# HammerHeadAFE.net
KiCad netlist of a schematic drawn in Altium Designer
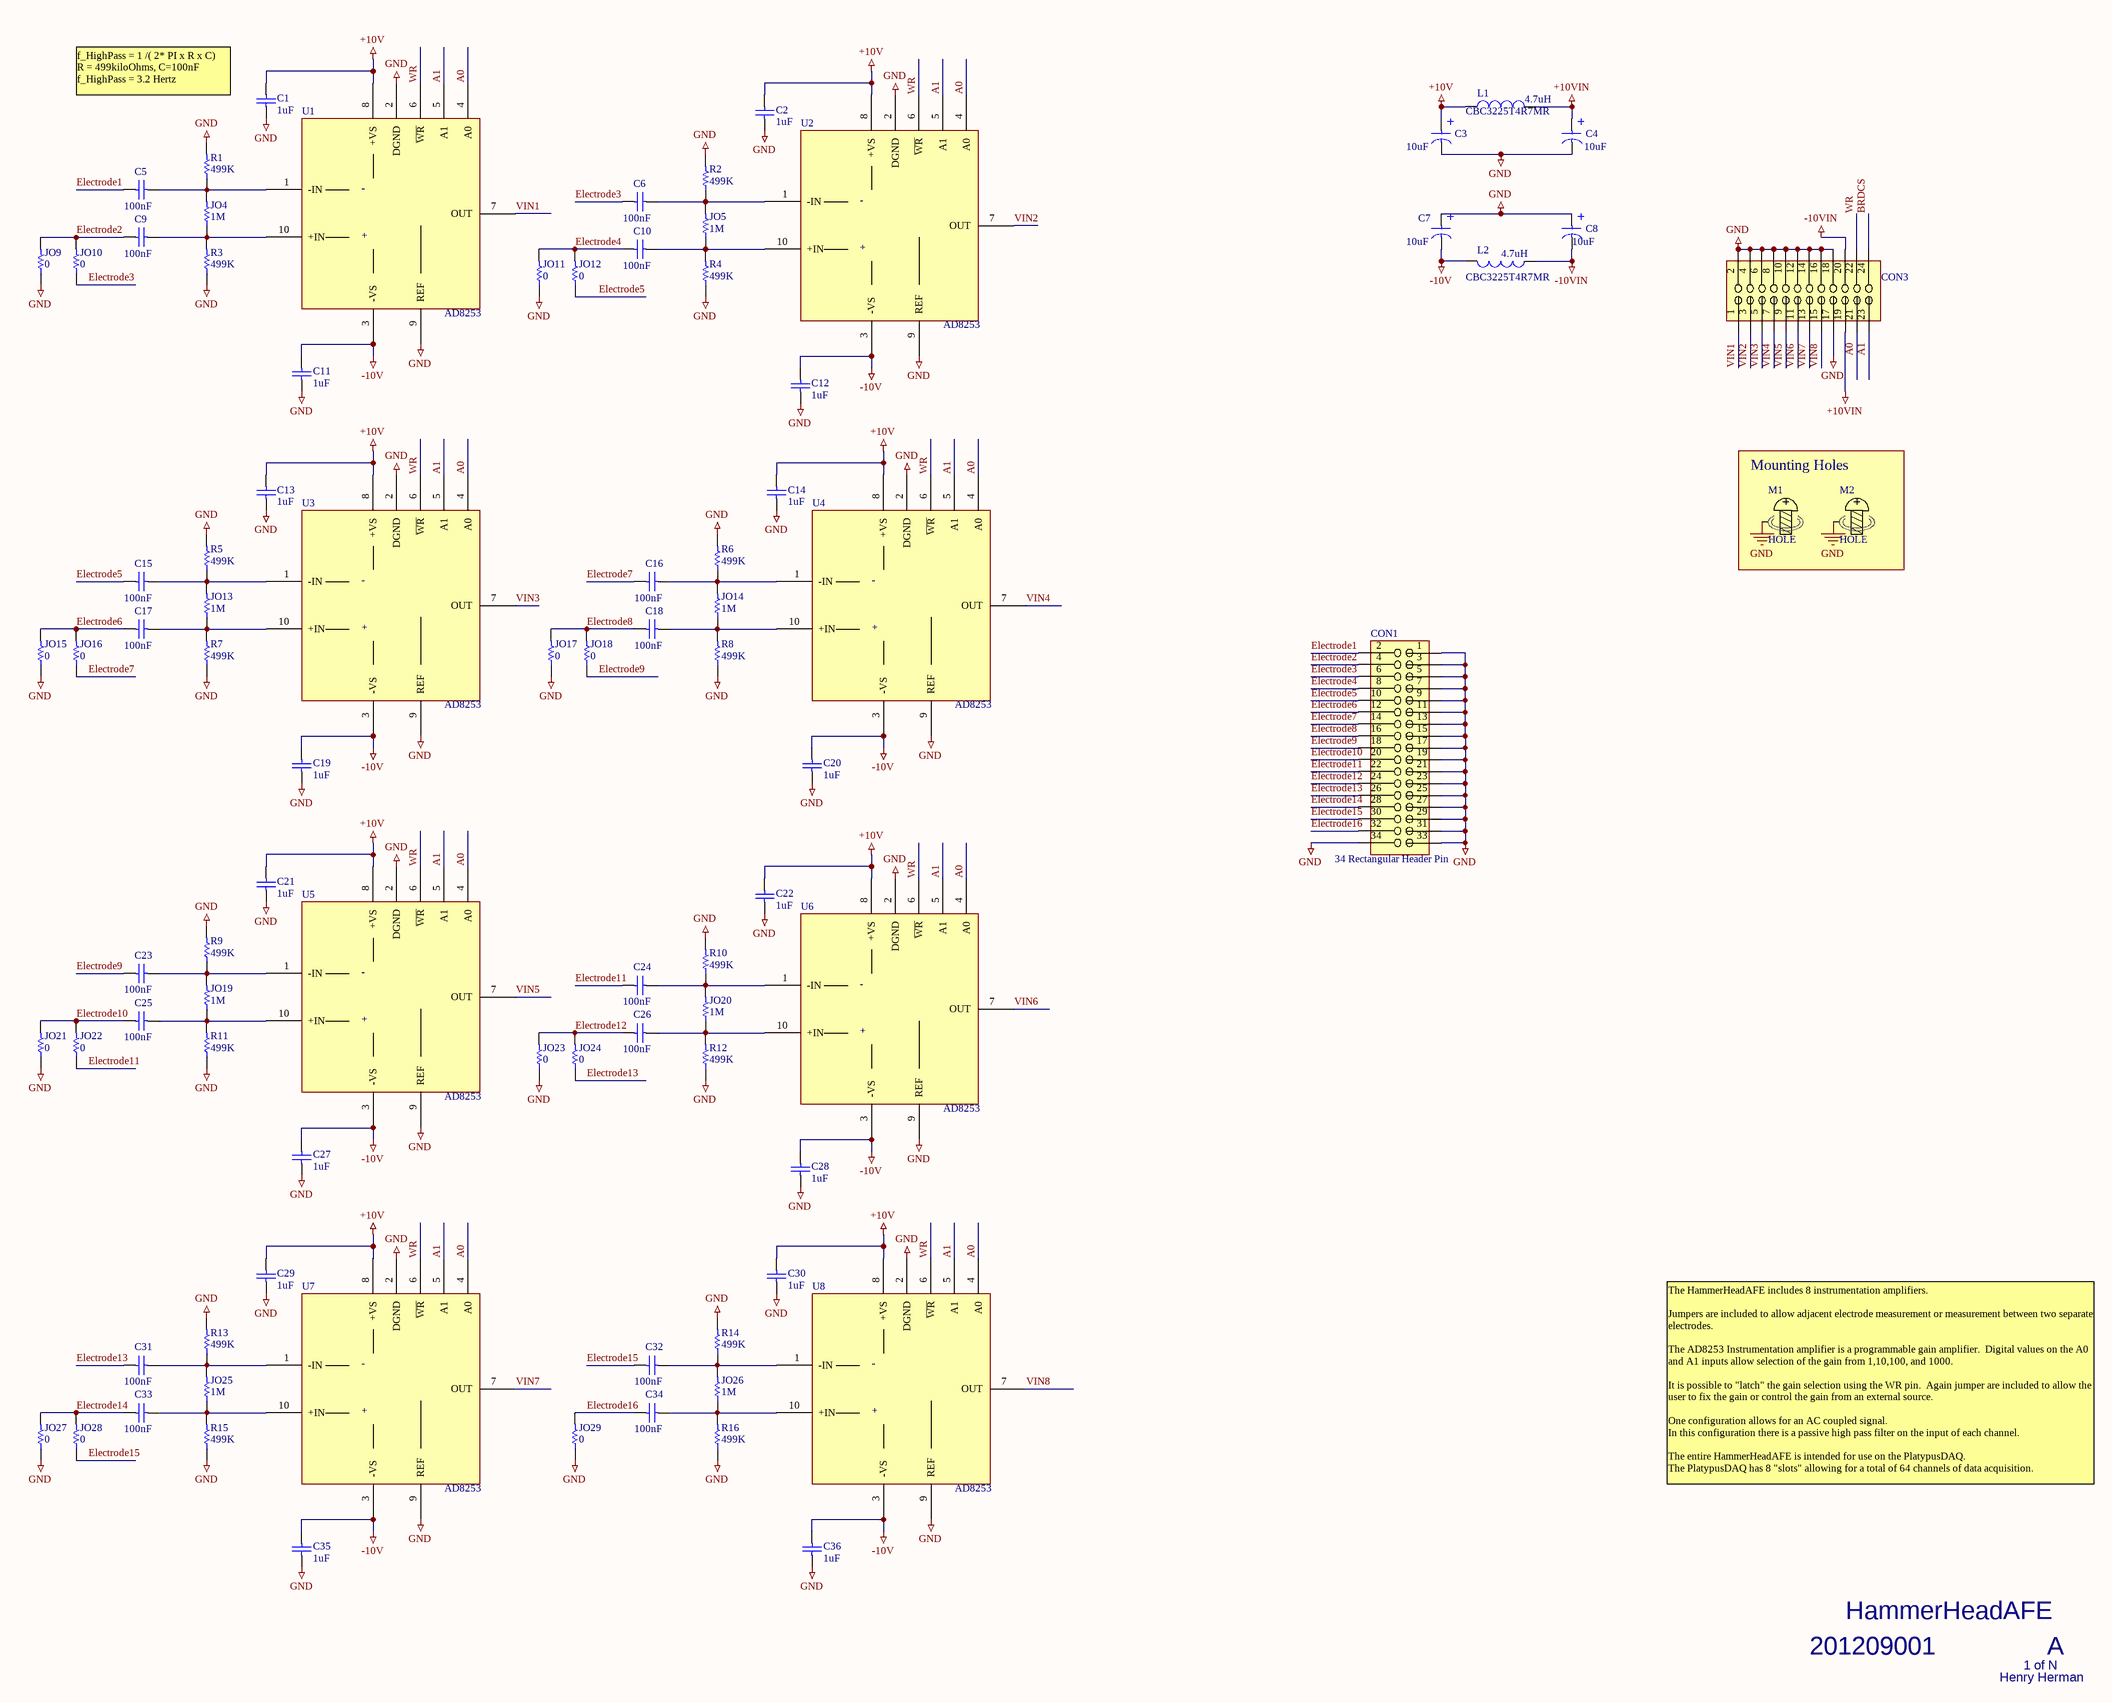
[diagram p0: HammerHeadAFE.SchDoc]

(export (version "E")
  (design (tool "Eeschema 10.0.6"))
  (components
    (comp (ref "C1")
      (value "CAP")
      (footprint "SM/C_0603")
      (description "1uF")
      (fields (field (name "LABEL") "1uF"))
      (libsource (lib "Henry1_20_2010") (part "CAP"))
    )
    (comp (ref "C2")
      (value "CAP")
      (footprint "SM/C_0603")
      (description "1uF")
      (fields (field (name "LABEL") "1uF"))
      (libsource (lib "Henry1_20_2010") (part "CAP"))
    )
    (comp (ref "C3")
      (value "CAP_POL")
      (footprint "SM/C_POL_0805")
      (description "CAP")
      (fields (field (name "LABEL") "10uF"))
      (libsource (lib "Henry1_20_2010") (part "CAP_POL"))
    )
    (comp (ref "C4")
      (value "CAP_POL")
      (footprint "SM/C_POL_0805")
      (description "CAP")
      (fields (field (name "LABEL") "10uF"))
      (libsource (lib "Henry1_20_2010") (part "CAP_POL"))
    )
    (comp (ref "C5")
      (value "CAP")
      (footprint "SM/C_0603")
      (description "100nF")
      (fields (field (name "LABEL") "100nF"))
      (libsource (lib "Henry1_20_2010") (part "CAP"))
    )
    (comp (ref "C6")
      (value "CAP")
      (footprint "SM/C_0603")
      (description "100nF")
      (fields (field (name "LABEL") "100nF"))
      (libsource (lib "Henry1_20_2010") (part "CAP"))
    )
    (comp (ref "C7")
      (value "CAP_POL")
      (footprint "SM/C_POL_0805")
      (description "CAP")
      (fields (field (name "LABEL") "10uF"))
      (libsource (lib "Henry1_20_2010") (part "CAP_POL"))
    )
    (comp (ref "C8")
      (value "CAP_POL")
      (footprint "SM/C_POL_0805")
      (description "CAP")
      (fields (field (name "LABEL") "10uF"))
      (libsource (lib "Henry1_20_2010") (part "CAP_POL"))
    )
    (comp (ref "C9")
      (value "CAP")
      (footprint "SM/C_0603")
      (description "100nF")
      (fields (field (name "LABEL") "100nF"))
      (libsource (lib "Henry1_20_2010") (part "CAP"))
    )
    (comp (ref "C10")
      (value "CAP")
      (footprint "SM/C_0603")
      (description "100nF")
      (fields (field (name "LABEL") "100nF"))
      (libsource (lib "Henry1_20_2010") (part "CAP"))
    )
    (comp (ref "C11")
      (value "CAP")
      (footprint "SM/C_0603")
      (description "1uF")
      (fields (field (name "LABEL") "1uF"))
      (libsource (lib "Henry1_20_2010") (part "CAP"))
    )
    (comp (ref "C12")
      (value "CAP")
      (footprint "SM/C_0603")
      (description "1uF")
      (fields (field (name "LABEL") "1uF"))
      (libsource (lib "Henry1_20_2010") (part "CAP"))
    )
    (comp (ref "C13")
      (value "CAP")
      (footprint "SM/C_0603")
      (description "1uF")
      (fields (field (name "LABEL") "1uF"))
      (libsource (lib "Henry1_20_2010") (part "CAP"))
    )
    (comp (ref "C14")
      (value "CAP")
      (footprint "SM/C_0603")
      (description "1uF")
      (fields (field (name "LABEL") "1uF"))
      (libsource (lib "Henry1_20_2010") (part "CAP"))
    )
    (comp (ref "C15")
      (value "CAP")
      (footprint "SM/C_0603")
      (description "100nF")
      (fields (field (name "LABEL") "100nF"))
      (libsource (lib "Henry1_20_2010") (part "CAP"))
    )
    (comp (ref "C16")
      (value "CAP")
      (footprint "SM/C_0603")
      (description "100nF")
      (fields (field (name "LABEL") "100nF"))
      (libsource (lib "Henry1_20_2010") (part "CAP"))
    )
    (comp (ref "C17")
      (value "CAP")
      (footprint "SM/C_0603")
      (description "100nF")
      (fields (field (name "LABEL") "100nF"))
      (libsource (lib "Henry1_20_2010") (part "CAP"))
    )
    (comp (ref "C18")
      (value "CAP")
      (footprint "SM/C_0603")
      (description "100nF")
      (fields (field (name "LABEL") "100nF"))
      (libsource (lib "Henry1_20_2010") (part "CAP"))
    )
    (comp (ref "C19")
      (value "CAP")
      (footprint "SM/C_0603")
      (description "1uF")
      (fields (field (name "LABEL") "1uF"))
      (libsource (lib "Henry1_20_2010") (part "CAP"))
    )
    (comp (ref "C20")
      (value "CAP")
      (footprint "SM/C_0603")
      (description "1uF")
      (fields (field (name "LABEL") "1uF"))
      (libsource (lib "Henry1_20_2010") (part "CAP"))
    )
    (comp (ref "C21")
      (value "CAP")
      (footprint "SM/C_0603")
      (description "1uF")
      (fields (field (name "LABEL") "1uF"))
      (libsource (lib "Henry1_20_2010") (part "CAP"))
    )
    (comp (ref "C22")
      (value "CAP")
      (footprint "SM/C_0603")
      (description "1uF")
      (fields (field (name "LABEL") "1uF"))
      (libsource (lib "Henry1_20_2010") (part "CAP"))
    )
    (comp (ref "C23")
      (value "CAP")
      (footprint "SM/C_0603")
      (description "100nF")
      (fields (field (name "LABEL") "100nF"))
      (libsource (lib "Henry1_20_2010") (part "CAP"))
    )
    (comp (ref "C24")
      (value "CAP")
      (footprint "SM/C_0603")
      (description "100nF")
      (fields (field (name "LABEL") "100nF"))
      (libsource (lib "Henry1_20_2010") (part "CAP"))
    )
    (comp (ref "C25")
      (value "CAP")
      (footprint "SM/C_0603")
      (description "100nF")
      (fields (field (name "LABEL") "100nF"))
      (libsource (lib "Henry1_20_2010") (part "CAP"))
    )
    (comp (ref "C26")
      (value "CAP")
      (footprint "SM/C_0603")
      (description "100nF")
      (fields (field (name "LABEL") "100nF"))
      (libsource (lib "Henry1_20_2010") (part "CAP"))
    )
    (comp (ref "C27")
      (value "CAP")
      (footprint "SM/C_0603")
      (description "1uF")
      (fields (field (name "LABEL") "1uF"))
      (libsource (lib "Henry1_20_2010") (part "CAP"))
    )
    (comp (ref "C28")
      (value "CAP")
      (footprint "SM/C_0603")
      (description "1uF")
      (fields (field (name "LABEL") "1uF"))
      (libsource (lib "Henry1_20_2010") (part "CAP"))
    )
    (comp (ref "C29")
      (value "CAP")
      (footprint "SM/C_0603")
      (description "1uF")
      (fields (field (name "LABEL") "1uF"))
      (libsource (lib "Henry1_20_2010") (part "CAP"))
    )
    (comp (ref "C30")
      (value "CAP")
      (footprint "SM/C_0603")
      (description "1uF")
      (fields (field (name "LABEL") "1uF"))
      (libsource (lib "Henry1_20_2010") (part "CAP"))
    )
    (comp (ref "C31")
      (value "CAP")
      (footprint "SM/C_0603")
      (description "100nF")
      (fields (field (name "LABEL") "100nF"))
      (libsource (lib "Henry1_20_2010") (part "CAP"))
    )
    (comp (ref "C32")
      (value "CAP")
      (footprint "SM/C_0603")
      (description "100nF")
      (fields (field (name "LABEL") "100nF"))
      (libsource (lib "Henry1_20_2010") (part "CAP"))
    )
    (comp (ref "C33")
      (value "CAP")
      (footprint "SM/C_0603")
      (description "100nF")
      (fields (field (name "LABEL") "100nF"))
      (libsource (lib "Henry1_20_2010") (part "CAP"))
    )
    (comp (ref "C34")
      (value "CAP")
      (footprint "SM/C_0603")
      (description "100nF")
      (fields (field (name "LABEL") "100nF"))
      (libsource (lib "Henry1_20_2010") (part "CAP"))
    )
    (comp (ref "C35")
      (value "CAP")
      (footprint "SM/C_0603")
      (description "1uF")
      (fields (field (name "LABEL") "1uF"))
      (libsource (lib "Henry1_20_2010") (part "CAP"))
    )
    (comp (ref "C36")
      (value "CAP")
      (footprint "SM/C_0603")
      (description "1uF")
      (fields (field (name "LABEL") "1uF"))
      (libsource (lib "Henry1_20_2010") (part "CAP"))
    )
    (comp (ref "CON1")
      (value "34 Rectangular Header Pin")
      (footprint "34Pin-Rectangular Header-SurfaceMount-100milSpacing")
      (libsource (lib "Henry1_20_2010") (part "34pinHeader"))
    )
    (comp (ref "CON3")
      (value "24pinHeader")
      (footprint "CONN-RECEPT-24PIN")
      (libsource (lib "Henry1_20_2010") (part "24pinHeader"))
    )
    (comp (ref "JO4")
      (value "1M")
      (footprint "SM/R_0603")
      (description "Resistor 1M")
      (fields (field (name "Comment") "Res") (field (name "PUBLISHER") "Altium Limited"))
      (libsource (lib "Henry1_20_2010") (part "Res"))
    )
    (comp (ref "JO5")
      (value "1M")
      (footprint "SM/R_0603")
      (description "Resistor 1M")
      (fields (field (name "Comment") "Res") (field (name "PUBLISHER") "Altium Limited"))
      (libsource (lib "Henry1_20_2010") (part "Res"))
    )
    (comp (ref "JO9")
      (value "0")
      (footprint "SM/R_0603")
      (description "Resistor")
      (fields (field (name "Comment") "Res") (field (name "PUBLISHER") "Altium Limited"))
      (libsource (lib "Henry1_20_2010") (part "Res"))
    )
    (comp (ref "JO10")
      (value "0")
      (footprint "SM/R_0603")
      (description "Resistor")
      (fields (field (name "Comment") "Res") (field (name "PUBLISHER") "Altium Limited"))
      (libsource (lib "Henry1_20_2010") (part "Res"))
    )
    (comp (ref "JO11")
      (value "0")
      (footprint "SM/R_0603")
      (description "Resistor")
      (fields (field (name "Comment") "Res") (field (name "PUBLISHER") "Altium Limited"))
      (libsource (lib "Henry1_20_2010") (part "Res"))
    )
    (comp (ref "JO12")
      (value "0")
      (footprint "SM/R_0603")
      (description "Resistor")
      (fields (field (name "Comment") "Res") (field (name "PUBLISHER") "Altium Limited"))
      (libsource (lib "Henry1_20_2010") (part "Res"))
    )
    (comp (ref "JO13")
      (value "1M")
      (footprint "SM/R_0603")
      (description "Resistor 1M")
      (fields (field (name "Comment") "Res") (field (name "PUBLISHER") "Altium Limited"))
      (libsource (lib "Henry1_20_2010") (part "Res"))
    )
    (comp (ref "JO14")
      (value "1M")
      (footprint "SM/R_0603")
      (description "Resistor 1M")
      (fields (field (name "Comment") "Res") (field (name "PUBLISHER") "Altium Limited"))
      (libsource (lib "Henry1_20_2010") (part "Res"))
    )
    (comp (ref "JO15")
      (value "0")
      (footprint "SM/R_0603")
      (description "Resistor")
      (fields (field (name "Comment") "Res") (field (name "PUBLISHER") "Altium Limited"))
      (libsource (lib "Henry1_20_2010") (part "Res"))
    )
    (comp (ref "JO16")
      (value "0")
      (footprint "SM/R_0603")
      (description "Resistor")
      (fields (field (name "Comment") "Res") (field (name "PUBLISHER") "Altium Limited"))
      (libsource (lib "Henry1_20_2010") (part "Res"))
    )
    (comp (ref "JO17")
      (value "0")
      (footprint "SM/R_0603")
      (description "Resistor")
      (fields (field (name "Comment") "Res") (field (name "PUBLISHER") "Altium Limited"))
      (libsource (lib "Henry1_20_2010") (part "Res"))
    )
    (comp (ref "JO18")
      (value "0")
      (footprint "SM/R_0603")
      (description "Resistor")
      (fields (field (name "Comment") "Res") (field (name "PUBLISHER") "Altium Limited"))
      (libsource (lib "Henry1_20_2010") (part "Res"))
    )
    (comp (ref "JO19")
      (value "1M")
      (footprint "SM/R_0603")
      (description "Resistor 1M")
      (fields (field (name "Comment") "Res") (field (name "PUBLISHER") "Altium Limited"))
      (libsource (lib "Henry1_20_2010") (part "Res"))
    )
    (comp (ref "JO20")
      (value "1M")
      (footprint "SM/R_0603")
      (description "Resistor 1M")
      (fields (field (name "Comment") "Res") (field (name "PUBLISHER") "Altium Limited"))
      (libsource (lib "Henry1_20_2010") (part "Res"))
    )
    (comp (ref "JO21")
      (value "0")
      (footprint "SM/R_0603")
      (description "Resistor")
      (fields (field (name "Comment") "Res") (field (name "PUBLISHER") "Altium Limited"))
      (libsource (lib "Henry1_20_2010") (part "Res"))
    )
    (comp (ref "JO22")
      (value "0")
      (footprint "SM/R_0603")
      (description "Resistor")
      (fields (field (name "Comment") "Res") (field (name "PUBLISHER") "Altium Limited"))
      (libsource (lib "Henry1_20_2010") (part "Res"))
    )
    (comp (ref "JO23")
      (value "0")
      (footprint "SM/R_0603")
      (description "Resistor")
      (fields (field (name "Comment") "Res") (field (name "PUBLISHER") "Altium Limited"))
      (libsource (lib "Henry1_20_2010") (part "Res"))
    )
    (comp (ref "JO24")
      (value "0")
      (footprint "SM/R_0603")
      (description "Resistor")
      (fields (field (name "Comment") "Res") (field (name "PUBLISHER") "Altium Limited"))
      (libsource (lib "Henry1_20_2010") (part "Res"))
    )
    (comp (ref "JO25")
      (value "1M")
      (footprint "SM/R_0603")
      (description "Resistor 1M")
      (fields (field (name "Comment") "Res") (field (name "PUBLISHER") "Altium Limited"))
      (libsource (lib "Henry1_20_2010") (part "Res"))
    )
    (comp (ref "JO26")
      (value "1M")
      (footprint "SM/R_0603")
      (description "Resistor 1M")
      (fields (field (name "Comment") "Res") (field (name "PUBLISHER") "Altium Limited"))
      (libsource (lib "Henry1_20_2010") (part "Res"))
    )
    (comp (ref "JO27")
      (value "0")
      (footprint "SM/R_0603")
      (description "Resistor")
      (fields (field (name "Comment") "Res") (field (name "PUBLISHER") "Altium Limited"))
      (libsource (lib "Henry1_20_2010") (part "Res"))
    )
    (comp (ref "JO28")
      (value "0")
      (footprint "SM/R_0603")
      (description "Resistor")
      (fields (field (name "Comment") "Res") (field (name "PUBLISHER") "Altium Limited"))
      (libsource (lib "Henry1_20_2010") (part "Res"))
    )
    (comp (ref "JO29")
      (value "0")
      (footprint "SM/R_0603")
      (description "Resistor")
      (fields (field (name "Comment") "Res") (field (name "PUBLISHER") "Altium Limited"))
      (libsource (lib "Henry1_20_2010") (part "Res"))
    )
    (comp (ref "L1")
      (value "CBC3225T4R7MR")
      (footprint "SM/L_0805")
      (fields (field (name "ALTIUM_VALUE") "4.7uH"))
      (libsource (lib "Henry1_20_2010") (part "Inductor"))
    )
    (comp (ref "L2")
      (value "CBC3225T4R7MR")
      (footprint "SM/L_0805")
      (fields (field (name "ALTIUM_VALUE") "4.7uH"))
      (libsource (lib "Henry1_20_2010") (part "Inductor"))
    )
    (comp (ref "M1")
      (value "HOLE")
      (footprint "MOUNTING_HOLE-125mil")
      (libsource (lib "Henry1_20_2010") (part "MountingHole"))
    )
    (comp (ref "M2")
      (value "HOLE")
      (footprint "MOUNTING_HOLE-125mil")
      (libsource (lib "Henry1_20_2010") (part "MountingHole"))
    )
    (comp (ref "R1")
      (value "499K")
      (footprint "SM/R_0603")
      (description "Resistor")
      (fields (field (name "Comment") "Res") (field (name "PUBLISHER") "Altium Limited"))
      (libsource (lib "Henry1_20_2010") (part "Res"))
    )
    (comp (ref "R2")
      (value "499K")
      (footprint "SM/R_0603")
      (description "Resistor")
      (fields (field (name "Comment") "Res") (field (name "PUBLISHER") "Altium Limited"))
      (libsource (lib "Henry1_20_2010") (part "Res"))
    )
    (comp (ref "R3")
      (value "499K")
      (footprint "SM/R_0603")
      (description "Resistor")
      (fields (field (name "Comment") "Res") (field (name "PUBLISHER") "Altium Limited"))
      (libsource (lib "Henry1_20_2010") (part "Res"))
    )
    (comp (ref "R4")
      (value "499K")
      (footprint "SM/R_0603")
      (description "Resistor")
      (fields (field (name "Comment") "Res") (field (name "PUBLISHER") "Altium Limited"))
      (libsource (lib "Henry1_20_2010") (part "Res"))
    )
    (comp (ref "R5")
      (value "499K")
      (footprint "SM/R_0603")
      (description "Resistor")
      (fields (field (name "Comment") "Res") (field (name "PUBLISHER") "Altium Limited"))
      (libsource (lib "Henry1_20_2010") (part "Res"))
    )
    (comp (ref "R6")
      (value "499K")
      (footprint "SM/R_0603")
      (description "Resistor")
      (fields (field (name "Comment") "Res") (field (name "PUBLISHER") "Altium Limited"))
      (libsource (lib "Henry1_20_2010") (part "Res"))
    )
    (comp (ref "R7")
      (value "499K")
      (footprint "SM/R_0603")
      (description "Resistor")
      (fields (field (name "Comment") "Res") (field (name "PUBLISHER") "Altium Limited"))
      (libsource (lib "Henry1_20_2010") (part "Res"))
    )
    (comp (ref "R8")
      (value "499K")
      (footprint "SM/R_0603")
      (description "Resistor")
      (fields (field (name "Comment") "Res") (field (name "PUBLISHER") "Altium Limited"))
      (libsource (lib "Henry1_20_2010") (part "Res"))
    )
    (comp (ref "R9")
      (value "499K")
      (footprint "SM/R_0603")
      (description "Resistor")
      (fields (field (name "Comment") "Res") (field (name "PUBLISHER") "Altium Limited"))
      (libsource (lib "Henry1_20_2010") (part "Res"))
    )
    (comp (ref "R10")
      (value "499K")
      (footprint "SM/R_0603")
      (description "Resistor")
      (fields (field (name "Comment") "Res") (field (name "PUBLISHER") "Altium Limited"))
      (libsource (lib "Henry1_20_2010") (part "Res"))
    )
    (comp (ref "R11")
      (value "499K")
      (footprint "SM/R_0603")
      (description "Resistor")
      (fields (field (name "Comment") "Res") (field (name "PUBLISHER") "Altium Limited"))
      (libsource (lib "Henry1_20_2010") (part "Res"))
    )
    (comp (ref "R12")
      (value "499K")
      (footprint "SM/R_0603")
      (description "Resistor")
      (fields (field (name "Comment") "Res") (field (name "PUBLISHER") "Altium Limited"))
      (libsource (lib "Henry1_20_2010") (part "Res"))
    )
    (comp (ref "R13")
      (value "499K")
      (footprint "SM/R_0603")
      (description "Resistor")
      (fields (field (name "Comment") "Res") (field (name "PUBLISHER") "Altium Limited"))
      (libsource (lib "Henry1_20_2010") (part "Res"))
    )
    (comp (ref "R14")
      (value "499K")
      (footprint "SM/R_0603")
      (description "Resistor")
      (fields (field (name "Comment") "Res") (field (name "PUBLISHER") "Altium Limited"))
      (libsource (lib "Henry1_20_2010") (part "Res"))
    )
    (comp (ref "R15")
      (value "499K")
      (footprint "SM/R_0603")
      (description "Resistor")
      (fields (field (name "Comment") "Res") (field (name "PUBLISHER") "Altium Limited"))
      (libsource (lib "Henry1_20_2010") (part "Res"))
    )
    (comp (ref "R16")
      (value "499K")
      (footprint "SM/R_0603")
      (description "Resistor")
      (fields (field (name "Comment") "Res") (field (name "PUBLISHER") "Altium Limited"))
      (libsource (lib "Henry1_20_2010") (part "Res"))
    )
    (comp (ref "U1")
      (value "AD8253")
      (footprint "MSOP-10-lead/AnalogDevices")
      (libsource (lib "Henry1_20_2010") (part "AD8253"))
    )
    (comp (ref "U2")
      (value "AD8253")
      (footprint "MSOP-10-lead/AnalogDevices")
      (libsource (lib "Henry1_20_2010") (part "AD8253"))
    )
    (comp (ref "U3")
      (value "AD8253")
      (footprint "MSOP-10-lead/AnalogDevices")
      (libsource (lib "Henry1_20_2010") (part "AD8253"))
    )
    (comp (ref "U4")
      (value "AD8253")
      (footprint "MSOP-10-lead/AnalogDevices")
      (libsource (lib "Henry1_20_2010") (part "AD8253"))
    )
    (comp (ref "U5")
      (value "AD8253")
      (footprint "MSOP-10-lead/AnalogDevices")
      (libsource (lib "Henry1_20_2010") (part "AD8253"))
    )
    (comp (ref "U6")
      (value "AD8253")
      (footprint "MSOP-10-lead/AnalogDevices")
      (libsource (lib "Henry1_20_2010") (part "AD8253"))
    )
    (comp (ref "U7")
      (value "AD8253")
      (footprint "MSOP-10-lead/AnalogDevices")
      (libsource (lib "Henry1_20_2010") (part "AD8253"))
    )
    (comp (ref "U8")
      (value "AD8253")
      (footprint "MSOP-10-lead/AnalogDevices")
      (libsource (lib "Henry1_20_2010") (part "AD8253"))
    )
  )
  (nets
    (net (code "1") (name "+10V") (class "Default")
      (node (ref "C1") (pin "1") (pinfunction "1_1") (pintype "passive"))
      (node (ref "C13") (pin "1") (pinfunction "1_1") (pintype "passive"))
      (node (ref "C14") (pin "1") (pinfunction "1_1") (pintype "passive"))
      (node (ref "C2") (pin "1") (pinfunction "1_1") (pintype "passive"))
      (node (ref "C21") (pin "1") (pinfunction "1_1") (pintype "passive"))
      (node (ref "C22") (pin "1") (pinfunction "1_1") (pintype "passive"))
      (node (ref "C29") (pin "1") (pinfunction "1_1") (pintype "passive"))
      (node (ref "C3") (pin "1") (pinfunction "1_1") (pintype "passive"))
      (node (ref "C30") (pin "1") (pinfunction "1_1") (pintype "passive"))
      (node (ref "L1") (pin "1") (pinfunction "1_1") (pintype "passive"))
      (node (ref "U1") (pin "8") (pinfunction "+VS_8") (pintype "passive"))
      (node (ref "U2") (pin "8") (pinfunction "+VS_8") (pintype "passive"))
      (node (ref "U3") (pin "8") (pinfunction "+VS_8") (pintype "passive"))
      (node (ref "U4") (pin "8") (pinfunction "+VS_8") (pintype "passive"))
      (node (ref "U5") (pin "8") (pinfunction "+VS_8") (pintype "passive"))
      (node (ref "U6") (pin "8") (pinfunction "+VS_8") (pintype "passive"))
      (node (ref "U7") (pin "8") (pinfunction "+VS_8") (pintype "passive"))
      (node (ref "U8") (pin "8") (pinfunction "+VS_8") (pintype "passive"))
    )
    (net (code "2") (name "+10VIN") (class "Default")
      (node (ref "C4") (pin "1") (pinfunction "1_1") (pintype "passive"))
      (node (ref "CON3") (pin "19") (pinfunction "19_19") (pintype "passive"))
      (node (ref "L1") (pin "2") (pinfunction "2_2") (pintype "passive"))
    )
    (net (code "3") (name "-10V") (class "Default")
      (node (ref "C11") (pin "1") (pinfunction "1_1") (pintype "passive"))
      (node (ref "C12") (pin "1") (pinfunction "1_1") (pintype "passive"))
      (node (ref "C19") (pin "1") (pinfunction "1_1") (pintype "passive"))
      (node (ref "C20") (pin "1") (pinfunction "1_1") (pintype "passive"))
      (node (ref "C27") (pin "1") (pinfunction "1_1") (pintype "passive"))
      (node (ref "C28") (pin "1") (pinfunction "1_1") (pintype "passive"))
      (node (ref "C35") (pin "1") (pinfunction "1_1") (pintype "passive"))
      (node (ref "C36") (pin "1") (pinfunction "1_1") (pintype "passive"))
      (node (ref "C7") (pin "2") (pinfunction "2_2") (pintype "passive"))
      (node (ref "L2") (pin "2") (pinfunction "2_2") (pintype "passive"))
      (node (ref "U1") (pin "3") (pinfunction "-VS_3") (pintype "passive"))
      (node (ref "U2") (pin "3") (pinfunction "-VS_3") (pintype "passive"))
      (node (ref "U3") (pin "3") (pinfunction "-VS_3") (pintype "passive"))
      (node (ref "U4") (pin "3") (pinfunction "-VS_3") (pintype "passive"))
      (node (ref "U5") (pin "3") (pinfunction "-VS_3") (pintype "passive"))
      (node (ref "U6") (pin "3") (pinfunction "-VS_3") (pintype "passive"))
      (node (ref "U7") (pin "3") (pinfunction "-VS_3") (pintype "passive"))
      (node (ref "U8") (pin "3") (pinfunction "-VS_3") (pintype "passive"))
    )
    (net (code "4") (name "-10VIN") (class "Default")
      (node (ref "C8") (pin "2") (pinfunction "2_2") (pintype "passive"))
      (node (ref "CON3") (pin "20") (pinfunction "20_20") (pintype "passive"))
      (node (ref "L2") (pin "1") (pinfunction "1_1") (pintype "passive"))
    )
    (net (code "5") (name "/A0") (class "Default")
      (node (ref "CON3") (pin "21") (pinfunction "21_21") (pintype "passive"))
      (node (ref "U1") (pin "4") (pinfunction "A0_4") (pintype "passive"))
      (node (ref "U2") (pin "4") (pinfunction "A0_4") (pintype "passive"))
      (node (ref "U3") (pin "4") (pinfunction "A0_4") (pintype "passive"))
      (node (ref "U4") (pin "4") (pinfunction "A0_4") (pintype "passive"))
      (node (ref "U5") (pin "4") (pinfunction "A0_4") (pintype "passive"))
      (node (ref "U6") (pin "4") (pinfunction "A0_4") (pintype "passive"))
      (node (ref "U7") (pin "4") (pinfunction "A0_4") (pintype "passive"))
      (node (ref "U8") (pin "4") (pinfunction "A0_4") (pintype "passive"))
    )
    (net (code "6") (name "/A1") (class "Default")
      (node (ref "CON3") (pin "23") (pinfunction "23_23") (pintype "passive"))
      (node (ref "U1") (pin "5") (pinfunction "A1_5") (pintype "passive"))
      (node (ref "U2") (pin "5") (pinfunction "A1_5") (pintype "passive"))
      (node (ref "U3") (pin "5") (pinfunction "A1_5") (pintype "passive"))
      (node (ref "U4") (pin "5") (pinfunction "A1_5") (pintype "passive"))
      (node (ref "U5") (pin "5") (pinfunction "A1_5") (pintype "passive"))
      (node (ref "U6") (pin "5") (pinfunction "A1_5") (pintype "passive"))
      (node (ref "U7") (pin "5") (pinfunction "A1_5") (pintype "passive"))
      (node (ref "U8") (pin "5") (pinfunction "A1_5") (pintype "passive"))
    )
    (net (code "7") (name "/BRDCS") (class "Default")
      (node (ref "CON3") (pin "24") (pinfunction "24_24") (pintype "passive"))
    )
    (net (code "8") (name "/Electrode1") (class "Default")
      (node (ref "C5") (pin "1") (pinfunction "1_1") (pintype "passive"))
      (node (ref "CON1") (pin "2") (pinfunction "2_2") (pintype "passive"))
    )
    (net (code "9") (name "/Electrode2") (class "Default")
      (node (ref "C9") (pin "1") (pinfunction "1_1") (pintype "passive"))
      (node (ref "CON1") (pin "4") (pinfunction "4_4") (pintype "passive"))
      (node (ref "JO10") (pin "2") (pinfunction "2_2") (pintype "passive"))
      (node (ref "JO9") (pin "2") (pinfunction "2_2") (pintype "passive"))
    )
    (net (code "10") (name "/Electrode3") (class "Default")
      (node (ref "C6") (pin "1") (pinfunction "1_1") (pintype "passive"))
      (node (ref "CON1") (pin "6") (pinfunction "6_6") (pintype "passive"))
      (node (ref "JO10") (pin "1") (pinfunction "1_1") (pintype "passive"))
    )
    (net (code "11") (name "/Electrode4") (class "Default")
      (node (ref "C10") (pin "1") (pinfunction "1_1") (pintype "passive"))
      (node (ref "CON1") (pin "8") (pinfunction "8_8") (pintype "passive"))
      (node (ref "JO11") (pin "2") (pinfunction "2_2") (pintype "passive"))
      (node (ref "JO12") (pin "2") (pinfunction "2_2") (pintype "passive"))
    )
    (net (code "12") (name "/Electrode5") (class "Default")
      (node (ref "C15") (pin "1") (pinfunction "1_1") (pintype "passive"))
      (node (ref "CON1") (pin "10") (pinfunction "10_10") (pintype "passive"))
      (node (ref "JO12") (pin "1") (pinfunction "1_1") (pintype "passive"))
    )
    (net (code "13") (name "/Electrode6") (class "Default")
      (node (ref "C17") (pin "1") (pinfunction "1_1") (pintype "passive"))
      (node (ref "CON1") (pin "12") (pinfunction "12_12") (pintype "passive"))
      (node (ref "JO15") (pin "2") (pinfunction "2_2") (pintype "passive"))
      (node (ref "JO16") (pin "2") (pinfunction "2_2") (pintype "passive"))
    )
    (net (code "14") (name "/Electrode7") (class "Default")
      (node (ref "C16") (pin "1") (pinfunction "1_1") (pintype "passive"))
      (node (ref "CON1") (pin "14") (pinfunction "14_14") (pintype "passive"))
      (node (ref "JO16") (pin "1") (pinfunction "1_1") (pintype "passive"))
    )
    (net (code "15") (name "/Electrode8") (class "Default")
      (node (ref "C18") (pin "1") (pinfunction "1_1") (pintype "passive"))
      (node (ref "CON1") (pin "16") (pinfunction "16_16") (pintype "passive"))
      (node (ref "JO17") (pin "2") (pinfunction "2_2") (pintype "passive"))
      (node (ref "JO18") (pin "2") (pinfunction "2_2") (pintype "passive"))
    )
    (net (code "16") (name "/Electrode9") (class "Default")
      (node (ref "C23") (pin "1") (pinfunction "1_1") (pintype "passive"))
      (node (ref "CON1") (pin "18") (pinfunction "18_18") (pintype "passive"))
      (node (ref "JO18") (pin "1") (pinfunction "1_1") (pintype "passive"))
    )
    (net (code "17") (name "/Electrode10") (class "Default")
      (node (ref "C25") (pin "1") (pinfunction "1_1") (pintype "passive"))
      (node (ref "CON1") (pin "20") (pinfunction "20_20") (pintype "passive"))
      (node (ref "JO21") (pin "2") (pinfunction "2_2") (pintype "passive"))
      (node (ref "JO22") (pin "2") (pinfunction "2_2") (pintype "passive"))
    )
    (net (code "18") (name "/Electrode11") (class "Default")
      (node (ref "C24") (pin "1") (pinfunction "1_1") (pintype "passive"))
      (node (ref "CON1") (pin "22") (pinfunction "22_22") (pintype "passive"))
      (node (ref "JO22") (pin "1") (pinfunction "1_1") (pintype "passive"))
    )
    (net (code "19") (name "/Electrode12") (class "Default")
      (node (ref "C26") (pin "1") (pinfunction "1_1") (pintype "passive"))
      (node (ref "CON1") (pin "24") (pinfunction "24_24") (pintype "passive"))
      (node (ref "JO23") (pin "2") (pinfunction "2_2") (pintype "passive"))
      (node (ref "JO24") (pin "2") (pinfunction "2_2") (pintype "passive"))
    )
    (net (code "20") (name "/Electrode13") (class "Default")
      (node (ref "C31") (pin "1") (pinfunction "1_1") (pintype "passive"))
      (node (ref "CON1") (pin "26") (pinfunction "26_26") (pintype "passive"))
      (node (ref "JO24") (pin "1") (pinfunction "1_1") (pintype "passive"))
    )
    (net (code "21") (name "/Electrode14") (class "Default")
      (node (ref "C33") (pin "1") (pinfunction "1_1") (pintype "passive"))
      (node (ref "CON1") (pin "28") (pinfunction "28_28") (pintype "passive"))
      (node (ref "JO27") (pin "2") (pinfunction "2_2") (pintype "passive"))
      (node (ref "JO28") (pin "2") (pinfunction "2_2") (pintype "passive"))
    )
    (net (code "22") (name "/Electrode15") (class "Default")
      (node (ref "C32") (pin "1") (pinfunction "1_1") (pintype "passive"))
      (node (ref "CON1") (pin "30") (pinfunction "30_30") (pintype "passive"))
      (node (ref "JO28") (pin "1") (pinfunction "1_1") (pintype "passive"))
    )
    (net (code "23") (name "/Electrode16") (class "Default")
      (node (ref "C34") (pin "1") (pinfunction "1_1") (pintype "passive"))
      (node (ref "CON1") (pin "32") (pinfunction "32_32") (pintype "passive"))
      (node (ref "JO29") (pin "2") (pinfunction "2_2") (pintype "passive"))
    )
    (net (code "24") (name "/VIN1") (class "Default")
      (node (ref "CON3") (pin "1") (pinfunction "1_1") (pintype "passive"))
      (node (ref "U1") (pin "7") (pinfunction "OUT_7") (pintype "passive"))
    )
    (net (code "25") (name "/VIN2") (class "Default")
      (node (ref "CON3") (pin "3") (pinfunction "3_3") (pintype "passive"))
      (node (ref "U2") (pin "7") (pinfunction "OUT_7") (pintype "passive"))
    )
    (net (code "26") (name "/VIN3") (class "Default")
      (node (ref "CON3") (pin "5") (pinfunction "5_5") (pintype "passive"))
      (node (ref "U3") (pin "7") (pinfunction "OUT_7") (pintype "passive"))
    )
    (net (code "27") (name "/VIN4") (class "Default")
      (node (ref "CON3") (pin "7") (pinfunction "7_7") (pintype "passive"))
      (node (ref "U4") (pin "7") (pinfunction "OUT_7") (pintype "passive"))
    )
    (net (code "28") (name "/VIN5") (class "Default")
      (node (ref "CON3") (pin "9") (pinfunction "9_9") (pintype "passive"))
      (node (ref "U5") (pin "7") (pinfunction "OUT_7") (pintype "passive"))
    )
    (net (code "29") (name "/VIN6") (class "Default")
      (node (ref "CON3") (pin "11") (pinfunction "11_11") (pintype "passive"))
      (node (ref "U6") (pin "7") (pinfunction "OUT_7") (pintype "passive"))
    )
    (net (code "30") (name "/VIN7") (class "Default")
      (node (ref "CON3") (pin "13") (pinfunction "13_13") (pintype "passive"))
      (node (ref "U7") (pin "7") (pinfunction "OUT_7") (pintype "passive"))
    )
    (net (code "31") (name "/VIN8") (class "Default")
      (node (ref "CON3") (pin "15") (pinfunction "15_15") (pintype "passive"))
      (node (ref "U8") (pin "7") (pinfunction "OUT_7") (pintype "passive"))
    )
    (net (code "32") (name "/WR") (class "Default")
      (node (ref "CON3") (pin "22") (pinfunction "22_22") (pintype "passive"))
      (node (ref "U1") (pin "6") (pinfunction "~{WR}_6") (pintype "passive"))
      (node (ref "U2") (pin "6") (pinfunction "~{WR}_6") (pintype "passive"))
      (node (ref "U3") (pin "6") (pinfunction "~{WR}_6") (pintype "passive"))
      (node (ref "U4") (pin "6") (pinfunction "~{WR}_6") (pintype "passive"))
      (node (ref "U5") (pin "6") (pinfunction "~{WR}_6") (pintype "passive"))
      (node (ref "U6") (pin "6") (pinfunction "~{WR}_6") (pintype "passive"))
      (node (ref "U7") (pin "6") (pinfunction "~{WR}_6") (pintype "passive"))
      (node (ref "U8") (pin "6") (pinfunction "~{WR}_6") (pintype "passive"))
    )
    (net (code "33") (name "GND") (class "Default")
      (node (ref "C1") (pin "2") (pinfunction "2_2") (pintype "passive"))
      (node (ref "C11") (pin "2") (pinfunction "2_2") (pintype "passive"))
      (node (ref "C12") (pin "2") (pinfunction "2_2") (pintype "passive"))
      (node (ref "C13") (pin "2") (pinfunction "2_2") (pintype "passive"))
      (node (ref "C14") (pin "2") (pinfunction "2_2") (pintype "passive"))
      (node (ref "C19") (pin "2") (pinfunction "2_2") (pintype "passive"))
      (node (ref "C2") (pin "2") (pinfunction "2_2") (pintype "passive"))
      (node (ref "C20") (pin "2") (pinfunction "2_2") (pintype "passive"))
      (node (ref "C21") (pin "2") (pinfunction "2_2") (pintype "passive"))
      (node (ref "C22") (pin "2") (pinfunction "2_2") (pintype "passive"))
      (node (ref "C27") (pin "2") (pinfunction "2_2") (pintype "passive"))
      (node (ref "C28") (pin "2") (pinfunction "2_2") (pintype "passive"))
      (node (ref "C29") (pin "2") (pinfunction "2_2") (pintype "passive"))
      (node (ref "C3") (pin "2") (pinfunction "2_2") (pintype "passive"))
      (node (ref "C30") (pin "2") (pinfunction "2_2") (pintype "passive"))
      (node (ref "C35") (pin "2") (pinfunction "2_2") (pintype "passive"))
      (node (ref "C36") (pin "2") (pinfunction "2_2") (pintype "passive"))
      (node (ref "C4") (pin "2") (pinfunction "2_2") (pintype "passive"))
      (node (ref "C7") (pin "1") (pinfunction "1_1") (pintype "passive"))
      (node (ref "C8") (pin "1") (pinfunction "1_1") (pintype "passive"))
      (node (ref "CON1") (pin "1") (pinfunction "1_1") (pintype "passive"))
      (node (ref "CON1") (pin "11") (pinfunction "11_11") (pintype "passive"))
      (node (ref "CON1") (pin "13") (pinfunction "13_13") (pintype "passive"))
      (node (ref "CON1") (pin "15") (pinfunction "15_15") (pintype "passive"))
      (node (ref "CON1") (pin "17") (pinfunction "17_17") (pintype "passive"))
      (node (ref "CON1") (pin "19") (pinfunction "19_19") (pintype "passive"))
      (node (ref "CON1") (pin "21") (pinfunction "21_21") (pintype "passive"))
      (node (ref "CON1") (pin "23") (pinfunction "23_23") (pintype "passive"))
      (node (ref "CON1") (pin "25") (pinfunction "25_25") (pintype "passive"))
      (node (ref "CON1") (pin "27") (pinfunction "27_27") (pintype "passive"))
      (node (ref "CON1") (pin "29") (pinfunction "29_29") (pintype "passive"))
      (node (ref "CON1") (pin "3") (pinfunction "3_3") (pintype "passive"))
      (node (ref "CON1") (pin "31") (pinfunction "31_31") (pintype "passive"))
      (node (ref "CON1") (pin "33") (pinfunction "33_33") (pintype "passive"))
      (node (ref "CON1") (pin "34") (pinfunction "34_34") (pintype "passive"))
      (node (ref "CON1") (pin "5") (pinfunction "5_5") (pintype "passive"))
      (node (ref "CON1") (pin "7") (pinfunction "7_7") (pintype "passive"))
      (node (ref "CON1") (pin "9") (pinfunction "9_9") (pintype "passive"))
      (node (ref "CON3") (pin "10") (pinfunction "10_10") (pintype "passive"))
      (node (ref "CON3") (pin "12") (pinfunction "12_12") (pintype "passive"))
      (node (ref "CON3") (pin "14") (pinfunction "14_14") (pintype "passive"))
      (node (ref "CON3") (pin "16") (pinfunction "16_16") (pintype "passive"))
      (node (ref "CON3") (pin "17") (pinfunction "17_17") (pintype "passive"))
      (node (ref "CON3") (pin "18") (pinfunction "18_18") (pintype "passive"))
      (node (ref "CON3") (pin "2") (pinfunction "2_2") (pintype "passive"))
      (node (ref "CON3") (pin "4") (pinfunction "4_4") (pintype "passive"))
      (node (ref "CON3") (pin "6") (pinfunction "6_6") (pintype "passive"))
      (node (ref "CON3") (pin "8") (pinfunction "8_8") (pintype "passive"))
      (node (ref "JO11") (pin "1") (pinfunction "1_1") (pintype "passive"))
      (node (ref "JO15") (pin "1") (pinfunction "1_1") (pintype "passive"))
      (node (ref "JO17") (pin "1") (pinfunction "1_1") (pintype "passive"))
      (node (ref "JO21") (pin "1") (pinfunction "1_1") (pintype "passive"))
      (node (ref "JO23") (pin "1") (pinfunction "1_1") (pintype "passive"))
      (node (ref "JO27") (pin "1") (pinfunction "1_1") (pintype "passive"))
      (node (ref "JO29") (pin "1") (pinfunction "1_1") (pintype "passive"))
      (node (ref "JO9") (pin "1") (pinfunction "1_1") (pintype "passive"))
      (node (ref "M1") (pin "0") (pinfunction "PAD_0") (pintype "power_in"))
      (node (ref "M2") (pin "0") (pinfunction "PAD_0") (pintype "power_in"))
      (node (ref "R1") (pin "2") (pinfunction "2_2") (pintype "passive"))
      (node (ref "R10") (pin "2") (pinfunction "2_2") (pintype "passive"))
      (node (ref "R11") (pin "1") (pinfunction "1_1") (pintype "passive"))
      (node (ref "R12") (pin "1") (pinfunction "1_1") (pintype "passive"))
      (node (ref "R13") (pin "2") (pinfunction "2_2") (pintype "passive"))
      (node (ref "R14") (pin "2") (pinfunction "2_2") (pintype "passive"))
      (node (ref "R15") (pin "1") (pinfunction "1_1") (pintype "passive"))
      (node (ref "R16") (pin "1") (pinfunction "1_1") (pintype "passive"))
      (node (ref "R2") (pin "2") (pinfunction "2_2") (pintype "passive"))
      (node (ref "R3") (pin "1") (pinfunction "1_1") (pintype "passive"))
      (node (ref "R4") (pin "1") (pinfunction "1_1") (pintype "passive"))
      (node (ref "R5") (pin "2") (pinfunction "2_2") (pintype "passive"))
      (node (ref "R6") (pin "2") (pinfunction "2_2") (pintype "passive"))
      (node (ref "R7") (pin "1") (pinfunction "1_1") (pintype "passive"))
      (node (ref "R8") (pin "1") (pinfunction "1_1") (pintype "passive"))
      (node (ref "R9") (pin "2") (pinfunction "2_2") (pintype "passive"))
      (node (ref "U1") (pin "2") (pinfunction "DGND_2") (pintype "passive"))
      (node (ref "U1") (pin "9") (pinfunction "REF_9") (pintype "passive"))
      (node (ref "U2") (pin "2") (pinfunction "DGND_2") (pintype "passive"))
      (node (ref "U2") (pin "9") (pinfunction "REF_9") (pintype "passive"))
      (node (ref "U3") (pin "2") (pinfunction "DGND_2") (pintype "passive"))
      (node (ref "U3") (pin "9") (pinfunction "REF_9") (pintype "passive"))
      (node (ref "U4") (pin "2") (pinfunction "DGND_2") (pintype "passive"))
      (node (ref "U4") (pin "9") (pinfunction "REF_9") (pintype "passive"))
      (node (ref "U5") (pin "2") (pinfunction "DGND_2") (pintype "passive"))
      (node (ref "U5") (pin "9") (pinfunction "REF_9") (pintype "passive"))
      (node (ref "U6") (pin "2") (pinfunction "DGND_2") (pintype "passive"))
      (node (ref "U6") (pin "9") (pinfunction "REF_9") (pintype "passive"))
      (node (ref "U7") (pin "2") (pinfunction "DGND_2") (pintype "passive"))
      (node (ref "U7") (pin "9") (pinfunction "REF_9") (pintype "passive"))
      (node (ref "U8") (pin "2") (pinfunction "DGND_2") (pintype "passive"))
      (node (ref "U8") (pin "9") (pinfunction "REF_9") (pintype "passive"))
    )
    (net (code "34") (name "Net-(U1-+IN)") (class "Default")
      (node (ref "C9") (pin "2") (pinfunction "2_2") (pintype "passive"))
      (node (ref "JO4") (pin "1") (pinfunction "1_1") (pintype "passive"))
      (node (ref "R3") (pin "2") (pinfunction "2_2") (pintype "passive"))
      (node (ref "U1") (pin "10") (pinfunction "+IN_10") (pintype "passive"))
    )
    (net (code "35") (name "Net-(U1--IN)") (class "Default")
      (node (ref "C5") (pin "2") (pinfunction "2_2") (pintype "passive"))
      (node (ref "JO4") (pin "2") (pinfunction "2_2") (pintype "passive"))
      (node (ref "R1") (pin "1") (pinfunction "1_1") (pintype "passive"))
      (node (ref "U1") (pin "1") (pinfunction "-IN_1") (pintype "passive"))
    )
    (net (code "36") (name "Net-(U2-+IN)") (class "Default")
      (node (ref "C10") (pin "2") (pinfunction "2_2") (pintype "passive"))
      (node (ref "JO5") (pin "1") (pinfunction "1_1") (pintype "passive"))
      (node (ref "R4") (pin "2") (pinfunction "2_2") (pintype "passive"))
      (node (ref "U2") (pin "10") (pinfunction "+IN_10") (pintype "passive"))
    )
    (net (code "37") (name "Net-(U2--IN)") (class "Default")
      (node (ref "C6") (pin "2") (pinfunction "2_2") (pintype "passive"))
      (node (ref "JO5") (pin "2") (pinfunction "2_2") (pintype "passive"))
      (node (ref "R2") (pin "1") (pinfunction "1_1") (pintype "passive"))
      (node (ref "U2") (pin "1") (pinfunction "-IN_1") (pintype "passive"))
    )
    (net (code "38") (name "Net-(U3-+IN)") (class "Default")
      (node (ref "C17") (pin "2") (pinfunction "2_2") (pintype "passive"))
      (node (ref "JO13") (pin "1") (pinfunction "1_1") (pintype "passive"))
      (node (ref "R7") (pin "2") (pinfunction "2_2") (pintype "passive"))
      (node (ref "U3") (pin "10") (pinfunction "+IN_10") (pintype "passive"))
    )
    (net (code "39") (name "Net-(U3--IN)") (class "Default")
      (node (ref "C15") (pin "2") (pinfunction "2_2") (pintype "passive"))
      (node (ref "JO13") (pin "2") (pinfunction "2_2") (pintype "passive"))
      (node (ref "R5") (pin "1") (pinfunction "1_1") (pintype "passive"))
      (node (ref "U3") (pin "1") (pinfunction "-IN_1") (pintype "passive"))
    )
    (net (code "40") (name "Net-(U4-+IN)") (class "Default")
      (node (ref "C18") (pin "2") (pinfunction "2_2") (pintype "passive"))
      (node (ref "JO14") (pin "1") (pinfunction "1_1") (pintype "passive"))
      (node (ref "R8") (pin "2") (pinfunction "2_2") (pintype "passive"))
      (node (ref "U4") (pin "10") (pinfunction "+IN_10") (pintype "passive"))
    )
    (net (code "41") (name "Net-(U4--IN)") (class "Default")
      (node (ref "C16") (pin "2") (pinfunction "2_2") (pintype "passive"))
      (node (ref "JO14") (pin "2") (pinfunction "2_2") (pintype "passive"))
      (node (ref "R6") (pin "1") (pinfunction "1_1") (pintype "passive"))
      (node (ref "U4") (pin "1") (pinfunction "-IN_1") (pintype "passive"))
    )
    (net (code "42") (name "Net-(U5-+IN)") (class "Default")
      (node (ref "C25") (pin "2") (pinfunction "2_2") (pintype "passive"))
      (node (ref "JO19") (pin "1") (pinfunction "1_1") (pintype "passive"))
      (node (ref "R11") (pin "2") (pinfunction "2_2") (pintype "passive"))
      (node (ref "U5") (pin "10") (pinfunction "+IN_10") (pintype "passive"))
    )
    (net (code "43") (name "Net-(U5--IN)") (class "Default")
      (node (ref "C23") (pin "2") (pinfunction "2_2") (pintype "passive"))
      (node (ref "JO19") (pin "2") (pinfunction "2_2") (pintype "passive"))
      (node (ref "R9") (pin "1") (pinfunction "1_1") (pintype "passive"))
      (node (ref "U5") (pin "1") (pinfunction "-IN_1") (pintype "passive"))
    )
    (net (code "44") (name "Net-(U6-+IN)") (class "Default")
      (node (ref "C26") (pin "2") (pinfunction "2_2") (pintype "passive"))
      (node (ref "JO20") (pin "1") (pinfunction "1_1") (pintype "passive"))
      (node (ref "R12") (pin "2") (pinfunction "2_2") (pintype "passive"))
      (node (ref "U6") (pin "10") (pinfunction "+IN_10") (pintype "passive"))
    )
    (net (code "45") (name "Net-(U6--IN)") (class "Default")
      (node (ref "C24") (pin "2") (pinfunction "2_2") (pintype "passive"))
      (node (ref "JO20") (pin "2") (pinfunction "2_2") (pintype "passive"))
      (node (ref "R10") (pin "1") (pinfunction "1_1") (pintype "passive"))
      (node (ref "U6") (pin "1") (pinfunction "-IN_1") (pintype "passive"))
    )
    (net (code "46") (name "Net-(U7-+IN)") (class "Default")
      (node (ref "C33") (pin "2") (pinfunction "2_2") (pintype "passive"))
      (node (ref "JO25") (pin "1") (pinfunction "1_1") (pintype "passive"))
      (node (ref "R15") (pin "2") (pinfunction "2_2") (pintype "passive"))
      (node (ref "U7") (pin "10") (pinfunction "+IN_10") (pintype "passive"))
    )
    (net (code "47") (name "Net-(U7--IN)") (class "Default")
      (node (ref "C31") (pin "2") (pinfunction "2_2") (pintype "passive"))
      (node (ref "JO25") (pin "2") (pinfunction "2_2") (pintype "passive"))
      (node (ref "R13") (pin "1") (pinfunction "1_1") (pintype "passive"))
      (node (ref "U7") (pin "1") (pinfunction "-IN_1") (pintype "passive"))
    )
    (net (code "48") (name "Net-(U8-+IN)") (class "Default")
      (node (ref "C34") (pin "2") (pinfunction "2_2") (pintype "passive"))
      (node (ref "JO26") (pin "1") (pinfunction "1_1") (pintype "passive"))
      (node (ref "R16") (pin "2") (pinfunction "2_2") (pintype "passive"))
      (node (ref "U8") (pin "10") (pinfunction "+IN_10") (pintype "passive"))
    )
    (net (code "49") (name "Net-(U8--IN)") (class "Default")
      (node (ref "C32") (pin "2") (pinfunction "2_2") (pintype "passive"))
      (node (ref "JO26") (pin "2") (pinfunction "2_2") (pintype "passive"))
      (node (ref "R14") (pin "1") (pinfunction "1_1") (pintype "passive"))
      (node (ref "U8") (pin "1") (pinfunction "-IN_1") (pintype "passive"))
    )
  )
)
